# Test_Board_for_NCP186-AMX330TAG_v01.net
KiCad netlist of a schematic drawn in EAGLE
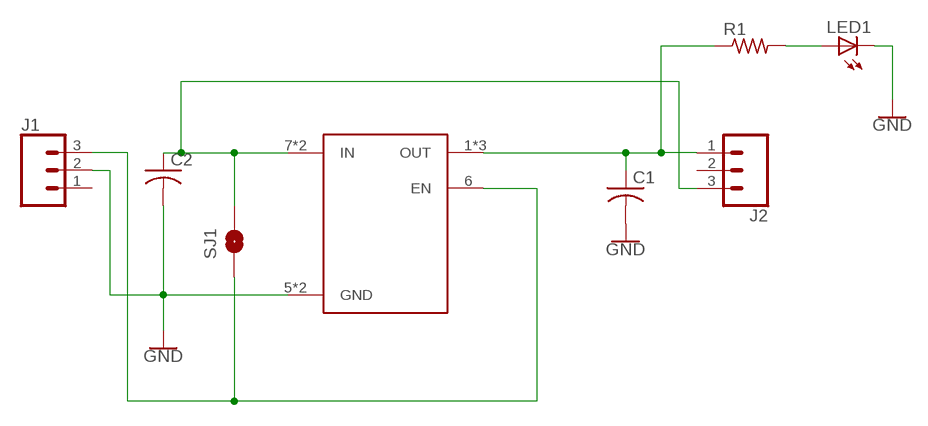
[diagram p0: schematic, sheet 1]

(export (version "E")
  (design (tool "Eeschema 10.0.6"))
  (components
    (comp (ref "C1")
      (value "C-USC0805K")
      (footprint "eagle-import:C0805K")
      (libsource (lib "eagle-import") (part "C-USC0805K"))
    )
    (comp (ref "C2")
      (value "C-USC0805K")
      (footprint "eagle-import:C0805K")
      (libsource (lib "eagle-import") (part "C-USC0805K"))
    )
    (comp (ref "J1")
      (value "CONN_03")
      (footprint "eagle-import:1X03")
      (libsource (lib "eagle-import") (part "CONN_03"))
    )
    (comp (ref "J2")
      (value "CONN_03")
      (footprint "eagle-import:1X03")
      (libsource (lib "eagle-import") (part "CONN_03"))
    )
    (comp (ref "LED1")
      (value "LEDCHIPLED_0603")
      (footprint "eagle-import:CHIPLED_0603")
      (libsource (lib "eagle-import") (part "LEDCHIPLED_0603"))
    )
    (comp (ref "R1")
      (value "R-US_R0805W")
      (footprint "eagle-import:R0805W")
      (libsource (lib "eagle-import") (part "R-US_R0805W"))
    )
    (comp (ref "SJ1")
      (value "SOLDERJUMPERNO")
      (footprint "eagle-import:SJ_2S-NO")
      (libsource (lib "eagle-import") (part "SOLDERJUMPERNO"))
    )
    (comp (ref "U$1")
      (value "NCP186-AMX330TAG")
      (footprint "eagle-import:XDFN8")
      (libsource (lib "eagle-import") (part "NCP186-AMX330TAG"))
    )
  )
  (nets
    (net (code "1") (name "GND") (class "Default")
      (node (ref "C1") (pin "2") (pinfunction "2_2") (pintype "passive"))
      (node (ref "C2") (pin "2") (pinfunction "2_2") (pintype "passive"))
      (node (ref "J1") (pin "2") (pinfunction "2_2") (pintype "passive"))
      (node (ref "LED1") (pin "C") (pinfunction "C_C") (pintype "passive"))
      (node (ref "U$1") (pin "5") (pinfunction "GND_5") (pintype "bidirectional"))
      (node (ref "U$1") (pin "PAD") (pinfunction "GND_PAD") (pintype "bidirectional"))
    )
    (net (code "2") (name "Net-(C1-Pad1)") (class "Default")
      (node (ref "C1") (pin "1") (pinfunction "1_1") (pintype "passive"))
      (node (ref "J2") (pin "1") (pinfunction "1_1") (pintype "passive"))
      (node (ref "R1") (pin "1") (pinfunction "1_1") (pintype "passive"))
      (node (ref "U$1") (pin "1") (pinfunction "OUT_1") (pintype "bidirectional"))
      (node (ref "U$1") (pin "2") (pinfunction "OUT_2") (pintype "bidirectional"))
      (node (ref "U$1") (pin "4") (pinfunction "OUT_4") (pintype "bidirectional"))
    )
    (net (code "3") (name "Net-(C2-Pad1)") (class "Default")
      (node (ref "C2") (pin "1") (pinfunction "1_1") (pintype "passive"))
      (node (ref "J2") (pin "3") (pinfunction "3_3") (pintype "passive"))
      (node (ref "SJ1") (pin "2") (pinfunction "2_2") (pintype "passive"))
      (node (ref "U$1") (pin "7") (pinfunction "IN_7") (pintype "bidirectional"))
      (node (ref "U$1") (pin "8") (pinfunction "IN_8") (pintype "bidirectional"))
    )
    (net (code "4") (name "Net-(LED1-PadA)") (class "Default")
      (node (ref "LED1") (pin "A") (pinfunction "A_A") (pintype "passive"))
      (node (ref "R1") (pin "2") (pinfunction "2_2") (pintype "passive"))
    )
    (net (code "5") (name "Net-(U$1-EN)") (class "Default")
      (node (ref "J1") (pin "3") (pinfunction "3_3") (pintype "passive"))
      (node (ref "SJ1") (pin "1") (pinfunction "1_1") (pintype "passive"))
      (node (ref "U$1") (pin "6") (pinfunction "EN_6") (pintype "bidirectional"))
    )
    (net (code "6") (name "unconnected-(J1-Pad1)") (class "Default")
      (node (ref "J1") (pin "1") (pinfunction "1_1") (pintype "passive"))
    )
    (net (code "7") (name "unconnected-(J2-Pad2)") (class "Default")
      (node (ref "J2") (pin "2") (pinfunction "2_2") (pintype "passive"))
    )
  )
)
